# Signal_switch.net
KiCad netlist of a schematic drawn in Altium Designer
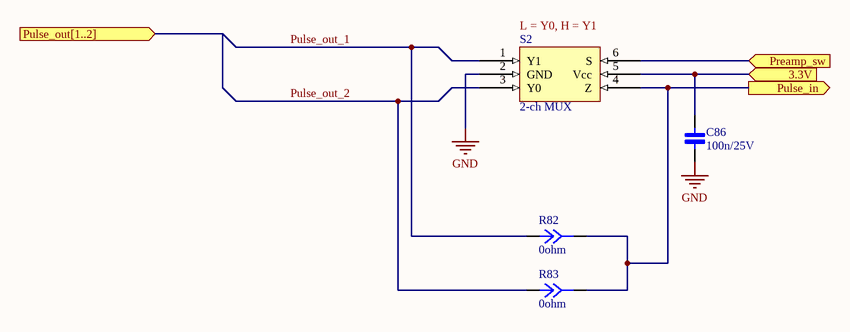
[diagram p0: Signal_switch.SchDoc]

(export (version "E")
  (design (tool "Eeschema 10.0.6"))
  (components
    (comp (ref "C86")
      (value "100n/25V")
      (footprint "CAP_0603")
      (description "Ceramic Capacitor 100n / 0603 / 25V / ±5%, Wurth Elektronik MLCC")
      (libsource (lib "Cubesat_lib") (part "Cap_0603_100n"))
    )
    (comp (ref "R82") (value "0ohm") (footprint "Jumper") (libsource (lib "Cubesat_lib") (part "Jumper")))
    (comp (ref "R83") (value "0ohm") (footprint "Jumper") (libsource (lib "Cubesat_lib") (part "Jumper")))
    (comp (ref "S2")
      (value "2-ch MUX")
      (footprint "TSOP6")
      (description "2-channel analog multiplexer/demultiplexernexperia")
      (libsource (lib "Cubesat_lib") (part "74LVC1G3157-Q100"))
    )
  )
  (nets
    (net (code "3") (name "/3.3V") (class "Default")
      (node (ref "C86") (pin "2") (pinfunction "2_2") (pintype "passive"))
      (node (ref "S2") (pin "5") (pinfunction "Vcc_5") (pintype "input"))
    )
    (net (code "4") (name "/Preamp_sw") (class "Default")
      (node (ref "S2") (pin "6") (pinfunction "S_6") (pintype "input"))
    )
    (net (code "5") (name "/Pulse_in") (class "Default")
      (node (ref "R82") (pin "2") (pinfunction "2_2") (pintype "passive"))
      (node (ref "R83") (pin "2") (pinfunction "2_2") (pintype "passive"))
      (node (ref "S2") (pin "4") (pinfunction "Z_4") (pintype "input"))
    )
    (net (code "7") (name "/Pulse_out_1") (class "Default")
      (node (ref "R82") (pin "2") (pinfunction "2_2") (pintype "passive"))
      (node (ref "S2") (pin "1") (pinfunction "Y1_1") (pintype "input"))
    )
    (net (code "8") (name "/Pulse_out_2") (class "Default")
      (node (ref "R83") (pin "2") (pinfunction "2_2") (pintype "passive"))
      (node (ref "S2") (pin "3") (pinfunction "Y0_3") (pintype "input"))
    )
    (net (code "9") (name "GND") (class "Default")
      (node (ref "C86") (pin "1") (pinfunction "1_1") (pintype "passive"))
      (node (ref "S2") (pin "2") (pinfunction "GND_2") (pintype "input"))
    )
  )
)
